# LEDs.net
KiCad netlist of a schematic drawn in Altium Designer
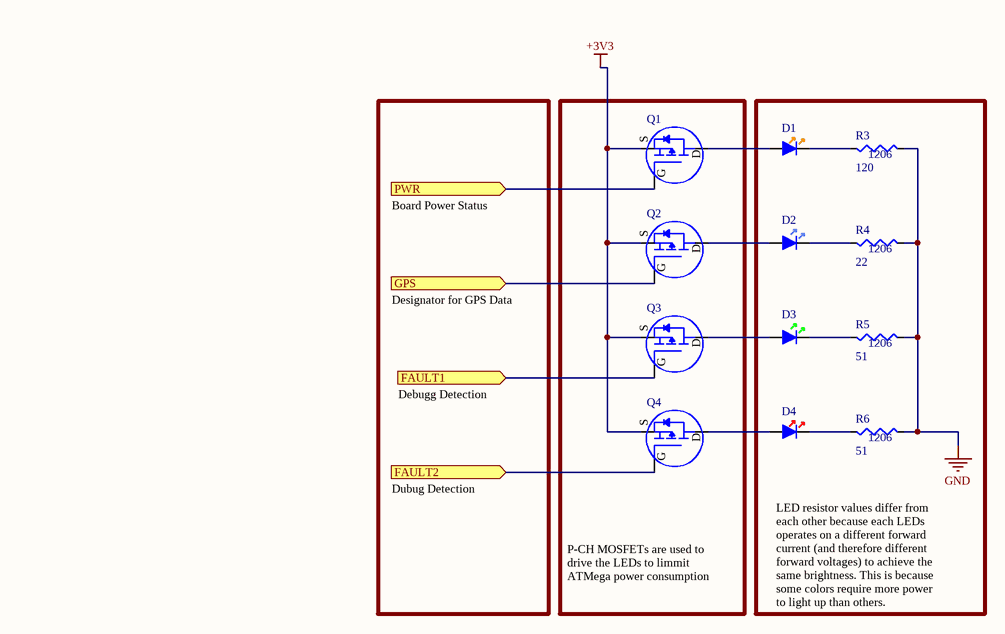
[diagram p0: LEDs.SchDoc]

(export (version "E")
  (design (tool "Eeschema 10.0.6"))
  (components
    (comp (ref "D1")
      (value "350-1556-ND")
      (footprint "350-1556-ND-Footprint-1")
      (description "LED ORANGE DIFFUSED 3MM T/H")
      (fields (field (name "MADE BY") "Elliott Meeks"))
      (libsource (lib "USCRPL") (part "350-1556-ND-Symbol-1"))
    )
    (comp (ref "D2")
      (value "151033BS03000")
      (footprint "Type 3mm")
      (description "Led, Blue, T-1 (3Mm), 470 Nm, 2.8 V, 30 Ma, 3.8 Cd Rohs Compliant: Yes")
      (libsource (lib "") (part "WE-LED_K1A2-2_1"))
    )
    (comp (ref "D3")
      (value "151031VS04000")
      (footprint "Type 3mm")
      (description "Led, Green, T-1 (3Mm), 570 Nm, 2.1 V, 30 Ma, 120 Mcd Rohs Compliant: Yes")
      (fields (field (name "MADE BY:") "Adam Lewczuk"))
      (libsource (lib "") (part "WE-LED_K1A2-2_1"))
    )
    (comp (ref "D4")
      (value "151031SS06000")
      (footprint "Type 3mm")
      (description "Led, Red, T-1 (3Mm), 630 Nm, 1.8 V, 30 Ma, 20 Mcd Rohs Compliant: Yes")
      (libsource (lib "USCRPL") (part "WE-LED_K1A2-2"))
    )
    (comp (ref "Q1")
      (value "BSS84")
      (footprint "SOT23")
      (description "MOSFET P-CH 50V 130MA SOT-23")
      (fields (field (name "MADE BY") "Brennan Swanton") (field (name "REVIEWED BY") "*"))
      (libsource (lib "USCRPL") (part "BSS84"))
    )
    (comp (ref "Q2")
      (value "BSS84")
      (footprint "SOT23")
      (description "MOSFET P-CH 50V 130MA SOT-23")
      (fields (field (name "MADE BY") "Brennan Swanton") (field (name "REVIEWED BY") "*"))
      (libsource (lib "USCRPL") (part "BSS84"))
    )
    (comp (ref "Q3")
      (value "BSS84")
      (footprint "SOT23")
      (description "MOSFET P-CH 50V 130MA SOT-23")
      (fields (field (name "MADE BY") "Brennan Swanton") (field (name "REVIEWED BY") "*"))
      (libsource (lib "USCRPL") (part "BSS84"))
    )
    (comp (ref "Q4")
      (value "BSS84")
      (footprint "SOT23")
      (description "MOSFET P-CH 50V 130MA SOT-23")
      (fields (field (name "MADE BY") "Brennan Swanton") (field (name "REVIEWED BY") "*"))
      (libsource (lib "USCRPL") (part "BSS84"))
    )
    (comp (ref "R3")
      (value "120")
      (footprint "R1206")
      (description "120 OHM 1% 1/4W 1206")
      (fields (field (name "REVIEWED BY") "Carter Allen") (field (name "MADE BY") "Brennan Swanton"))
      (libsource (lib "USCRPL") (part "Symbol"))
    )
    (comp (ref "R4")
      (value "22")
      (footprint "R1206")
      (description "22 OHM 1% 1/4W 1206")
      (fields (field (name "REVIEWED BY") "Carter Allen") (field (name "MADE BY") "Brennan Swanton"))
      (libsource (lib "USCRPL") (part "Symbol"))
    )
    (comp (ref "R5")
      (value "51")
      (footprint "R1206")
      (description "51 OHM 1% 1/4W 1206")
      (fields (field (name "MADE BY") "Jamie Smith"))
      (libsource (lib "USCRPL") (part "Symbol"))
    )
    (comp (ref "R6")
      (value "51")
      (footprint "R1206")
      (description "51 OHM 1% 1/4W 1206")
      (fields (field (name "MADE BY") "Jamie Smith"))
      (libsource (lib "USCRPL") (part "Symbol"))
    )
  )
  (nets
    (net (code "1") (name "+3V3") (class "Default")
      (node (ref "Q1") (pin "2") (pinfunction "S_2") (pintype "passive"))
      (node (ref "Q2") (pin "2") (pinfunction "S_2") (pintype "passive"))
      (node (ref "Q3") (pin "2") (pinfunction "S_2") (pintype "passive"))
      (node (ref "Q4") (pin "2") (pinfunction "S_2") (pintype "passive"))
    )
    (net (code "2") (name "/FAULT1") (class "Default")
      (node (ref "Q3") (pin "1") (pinfunction "G_1") (pintype "passive"))
    )
    (net (code "3") (name "/FAULT2") (class "Default")
      (node (ref "Q4") (pin "1") (pinfunction "G_1") (pintype "passive"))
    )
    (net (code "4") (name "/GPS") (class "Default")
      (node (ref "Q2") (pin "1") (pinfunction "G_1") (pintype "passive"))
    )
    (net (code "5") (name "/PWR") (class "Default")
      (node (ref "Q1") (pin "1") (pinfunction "G_1") (pintype "passive"))
    )
    (net (code "6") (name "GND") (class "Default")
      (node (ref "R3") (pin "2") (pinfunction "2_2") (pintype "passive"))
      (node (ref "R4") (pin "2") (pinfunction "2_2") (pintype "passive"))
      (node (ref "R5") (pin "2") (pinfunction "2_2") (pintype "passive"))
      (node (ref "R6") (pin "2") (pinfunction "2_2") (pintype "passive"))
    )
    (net (code "7") (name "Net-(D1-Pad1)") (class "Default")
      (node (ref "D1") (pin "1") (pinfunction "1_1") (pintype "passive"))
      (node (ref "R3") (pin "1") (pinfunction "1_1") (pintype "passive"))
    )
    (net (code "8") (name "Net-(D2-Pad1)") (class "Default")
      (node (ref "D2") (pin "1") (pinfunction "1_1") (pintype "passive"))
      (node (ref "R4") (pin "1") (pinfunction "1_1") (pintype "passive"))
    )
    (net (code "9") (name "Net-(D3-Pad1)") (class "Default")
      (node (ref "D3") (pin "1") (pinfunction "1_1") (pintype "passive"))
      (node (ref "R5") (pin "1") (pinfunction "1_1") (pintype "passive"))
    )
    (net (code "10") (name "Net-(D4-Pad1)") (class "Default")
      (node (ref "D4") (pin "1") (pinfunction "1_1") (pintype "passive"))
      (node (ref "R6") (pin "1") (pinfunction "1_1") (pintype "passive"))
    )
    (net (code "11") (name "Net-(Q1-D)") (class "Default")
      (node (ref "D1") (pin "2") (pinfunction "2_2") (pintype "passive"))
      (node (ref "Q1") (pin "3") (pinfunction "D_3") (pintype "passive"))
    )
    (net (code "12") (name "Net-(Q2-D)") (class "Default")
      (node (ref "D2") (pin "2") (pinfunction "2_2") (pintype "passive"))
      (node (ref "Q2") (pin "3") (pinfunction "D_3") (pintype "passive"))
    )
    (net (code "13") (name "Net-(Q3-D)") (class "Default")
      (node (ref "D3") (pin "2") (pinfunction "2_2") (pintype "passive"))
      (node (ref "Q3") (pin "3") (pinfunction "D_3") (pintype "passive"))
    )
    (net (code "14") (name "Net-(Q4-D)") (class "Default")
      (node (ref "D4") (pin "2") (pinfunction "2_2") (pintype "passive"))
      (node (ref "Q4") (pin "3") (pinfunction "D_3") (pintype "passive"))
    )
  )
)
